# -5v_Regulator.net
KiCad netlist of a schematic drawn in Altium Designer
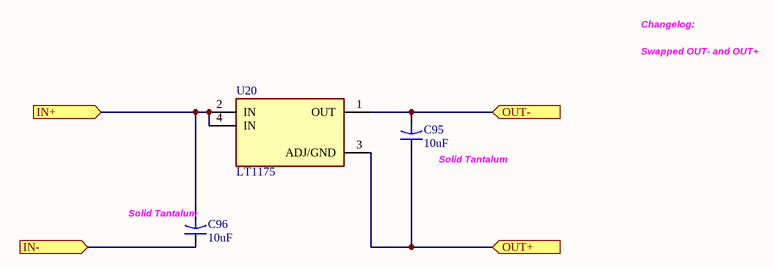
[diagram p0: -5v_Regulator.SchDoc]

(export (version "E")
  (design (tool "Eeschema 10.0.6"))
  (components
    (comp (ref "C95")
      (value "10uF")
      (footprint "Tantalum_2917")
      (description "Capacitor, 100uF NICHICON")
      (libsource (lib "Arturo_Approved") (part "UVR1V102MHD1TO"))
    )
    (comp (ref "C96")
      (value "10uF")
      (footprint "Tantalum_2917")
      (description "Capacitor, 100uF NICHICON")
      (libsource (lib "Arturo_Approved") (part "UVR1V102MHD1TO"))
    )
    (comp (ref "U20")
      (value "LT1175")
      (footprint "REG_LT1117IST-5#PBF")
      (libsource (lib "Arturo_Approved") (part "LT1175"))
    )
  )
  (nets
    (net (code "1") (name "/IN+") (class "Default")
      (node (ref "C96") (pin "2") (pinfunction "2_2") (pintype "passive"))
      (node (ref "U20") (pin "2") (pinfunction "IN_2") (pintype "passive"))
      (node (ref "U20") (pin "4") (pinfunction "IN_4") (pintype "passive"))
    )
    (net (code "2") (name "/IN-") (class "Default")
      (node (ref "C96") (pin "1") (pinfunction "1_1") (pintype "passive"))
    )
    (net (code "3") (name "/OUT+") (class "Default")
      (node (ref "C95") (pin "1") (pinfunction "1_1") (pintype "passive"))
      (node (ref "U20") (pin "3") (pinfunction "ADJ/GND_3") (pintype "power_in"))
    )
    (net (code "4") (name "/OUT-") (class "Default")
      (node (ref "C95") (pin "2") (pinfunction "2_2") (pintype "passive"))
      (node (ref "U20") (pin "1") (pinfunction "OUT_1") (pintype "passive"))
    )
  )
)
